# LPCB224_-_PI.net
KiCad netlist of a schematic drawn in Altium Designer
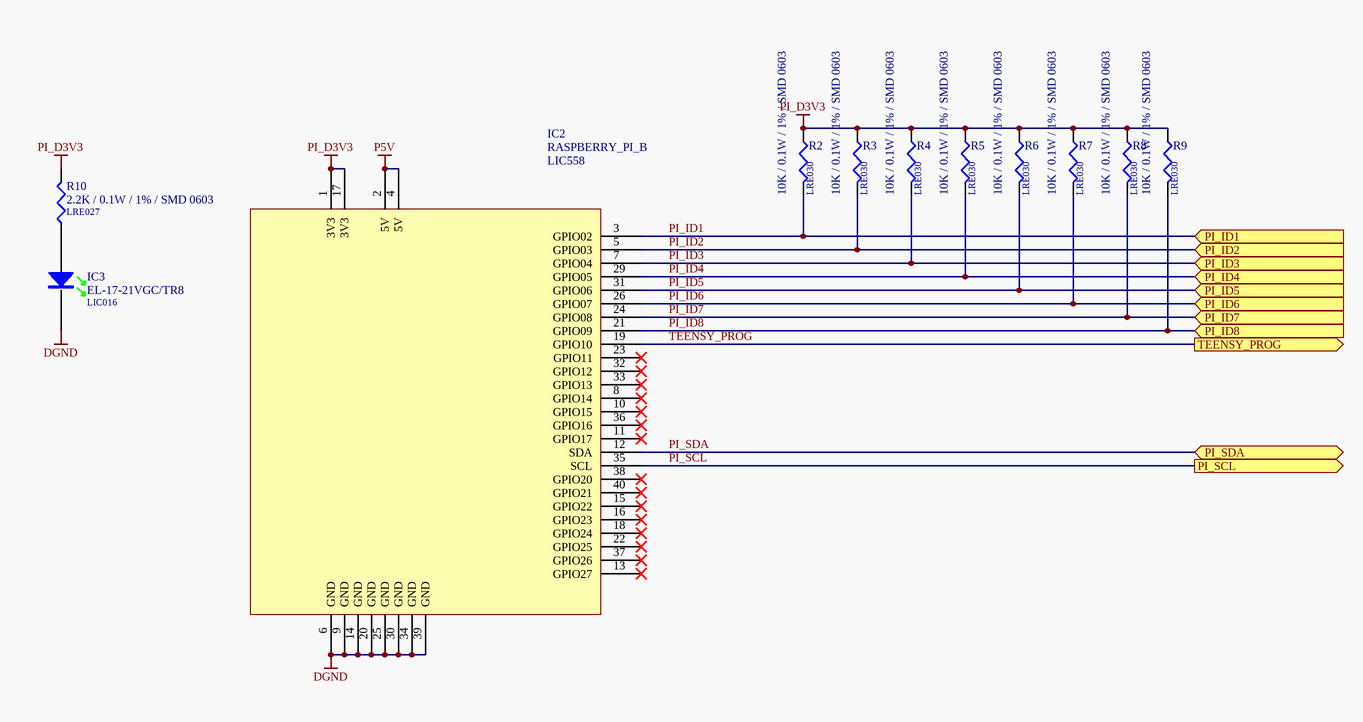
[diagram p0: LPCB224 - PI.SchDoc]

(export (version "E")
  (design (tool "Eeschema 10.0.6"))
  (components
    (comp (ref "IC2")
      (value "RASPBERRY_PI_B")
      (footprint "RASPBERRY_PI_B")
      (description "Raspberry Pi Model B")
      (fields (field (name "LDL_NUMBER") "LIC558"))
      (libsource (lib "LDL_Semiconductors") (part "RASPBERRY_PI_B"))
    )
    (comp (ref "IC3")
      (value "EL-17-21VGC/TR8")
      (footprint "CR2012-0805-LED")
      (description "LED, SMD, 0805 Green [LIC016]")
      (fields (field (name "LDL_NUMBER") "LIC016"))
      (libsource (lib "LDL_Semiconductors") (part "EL-17-21VGC/TR8"))
    )
    (comp (ref "R2")
      (value "10K / 0.1W / 1% / SMD 0603")
      (footprint "LFP020__CR1608-0603-IPC7351_B")
      (description "Resistor, Ceramic Chip, 10K, 0.1W, 1%, SMD 0603 [LRE030]")
      (fields (field (name "LDL_NUMBER") "LRE030"))
      (libsource (lib "LDL_Resistors") (part "10K / 0.1W / 1% / SMD 0603"))
    )
    (comp (ref "R3")
      (value "10K / 0.1W / 1% / SMD 0603")
      (footprint "LFP020__CR1608-0603-IPC7351_B")
      (description "Resistor, Ceramic Chip, 10K, 0.1W, 1%, SMD 0603 [LRE030]")
      (fields (field (name "LDL_NUMBER") "LRE030"))
      (libsource (lib "LDL_Resistors") (part "10K / 0.1W / 1% / SMD 0603"))
    )
    (comp (ref "R4")
      (value "10K / 0.1W / 1% / SMD 0603")
      (footprint "LFP020__CR1608-0603-IPC7351_B")
      (description "Resistor, Ceramic Chip, 10K, 0.1W, 1%, SMD 0603 [LRE030]")
      (fields (field (name "LDL_NUMBER") "LRE030"))
      (libsource (lib "LDL_Resistors") (part "10K / 0.1W / 1% / SMD 0603"))
    )
    (comp (ref "R5")
      (value "10K / 0.1W / 1% / SMD 0603")
      (footprint "LFP020__CR1608-0603-IPC7351_B")
      (description "Resistor, Ceramic Chip, 10K, 0.1W, 1%, SMD 0603 [LRE030]")
      (fields (field (name "LDL_NUMBER") "LRE030"))
      (libsource (lib "LDL_Resistors") (part "10K / 0.1W / 1% / SMD 0603"))
    )
    (comp (ref "R6")
      (value "10K / 0.1W / 1% / SMD 0603")
      (footprint "LFP020__CR1608-0603-IPC7351_B")
      (description "Resistor, Ceramic Chip, 10K, 0.1W, 1%, SMD 0603 [LRE030]")
      (fields (field (name "LDL_NUMBER") "LRE030"))
      (libsource (lib "LDL_Resistors") (part "10K / 0.1W / 1% / SMD 0603"))
    )
    (comp (ref "R7")
      (value "10K / 0.1W / 1% / SMD 0603")
      (footprint "LFP020__CR1608-0603-IPC7351_B")
      (description "Resistor, Ceramic Chip, 10K, 0.1W, 1%, SMD 0603 [LRE030]")
      (fields (field (name "LDL_NUMBER") "LRE030"))
      (libsource (lib "LDL_Resistors") (part "10K / 0.1W / 1% / SMD 0603"))
    )
    (comp (ref "R8")
      (value "10K / 0.1W / 1% / SMD 0603")
      (footprint "LFP020__CR1608-0603-IPC7351_B")
      (description "Resistor, Ceramic Chip, 10K, 0.1W, 1%, SMD 0603 [LRE030]")
      (fields (field (name "LDL_NUMBER") "LRE030"))
      (libsource (lib "LDL_Resistors") (part "10K / 0.1W / 1% / SMD 0603"))
    )
    (comp (ref "R9")
      (value "10K / 0.1W / 1% / SMD 0603")
      (footprint "LFP020__CR1608-0603-IPC7351_B")
      (description "Resistor, Ceramic Chip, 10K, 0.1W, 1%, SMD 0603 [LRE030]")
      (fields (field (name "LDL_NUMBER") "LRE030"))
      (libsource (lib "LDL_Resistors") (part "10K / 0.1W / 1% / SMD 0603"))
    )
    (comp (ref "R10")
      (value "2.2K / 0.1W / 1% / SMD 0603")
      (footprint "LFP020__CR1608-0603-IPC7351_B")
      (description "Resistor, Ceramic Chip, 2.2K, 0.1W, 1%, SMD 0603 [LRE027]")
      (fields (field (name "LDL_NUMBER") "LRE027"))
      (libsource (lib "LDL_Resistors") (part "2.2K / 0.1W / 1% / SMD 0603"))
    )
  )
  (nets
    (net (code "1") (name "/PI_ID1") (class "Default")
      (node (ref "IC2") (pin "3") (pinfunction "GPIO02_3") (pintype "passive"))
      (node (ref "R2") (pin "2") (pintype "passive"))
    )
    (net (code "2") (name "/PI_ID2") (class "Default")
      (node (ref "IC2") (pin "5") (pinfunction "GPIO03_5") (pintype "passive"))
      (node (ref "R3") (pin "2") (pintype "passive"))
    )
    (net (code "3") (name "/PI_ID3") (class "Default")
      (node (ref "IC2") (pin "7") (pinfunction "GPIO04_7") (pintype "passive"))
      (node (ref "R4") (pin "2") (pintype "passive"))
    )
    (net (code "4") (name "/PI_ID4") (class "Default")
      (node (ref "IC2") (pin "29") (pinfunction "GPIO05_29") (pintype "passive"))
      (node (ref "R5") (pin "2") (pintype "passive"))
    )
    (net (code "5") (name "/PI_ID5") (class "Default")
      (node (ref "IC2") (pin "31") (pinfunction "GPIO06_31") (pintype "passive"))
      (node (ref "R6") (pin "2") (pintype "passive"))
    )
    (net (code "6") (name "/PI_ID6") (class "Default")
      (node (ref "IC2") (pin "26") (pinfunction "GPIO07_26") (pintype "passive"))
      (node (ref "R7") (pin "2") (pintype "passive"))
    )
    (net (code "7") (name "/PI_ID7") (class "Default")
      (node (ref "IC2") (pin "24") (pinfunction "GPIO08_24") (pintype "passive"))
      (node (ref "R8") (pin "2") (pintype "passive"))
    )
    (net (code "8") (name "/PI_ID8") (class "Default")
      (node (ref "IC2") (pin "21") (pinfunction "GPIO09_21") (pintype "passive"))
      (node (ref "R9") (pin "2") (pintype "passive"))
    )
    (net (code "9") (name "/PI_SCL") (class "Default")
      (node (ref "IC2") (pin "35") (pinfunction "SCL_35") (pintype "passive"))
    )
    (net (code "10") (name "/PI_SDA") (class "Default")
      (node (ref "IC2") (pin "12") (pinfunction "SDA_12") (pintype "passive"))
    )
    (net (code "11") (name "/TEENSY_PROG") (class "Default")
      (node (ref "IC2") (pin "19") (pinfunction "GPIO10_19") (pintype "passive"))
    )
    (net (code "12") (name "DGND") (class "Default")
      (node (ref "IC2") (pin "14") (pinfunction "GND_14") (pintype "power_in"))
      (node (ref "IC2") (pin "20") (pinfunction "GND_20") (pintype "power_in"))
      (node (ref "IC2") (pin "25") (pinfunction "GND_25") (pintype "power_in"))
      (node (ref "IC2") (pin "30") (pinfunction "GND_30") (pintype "power_in"))
      (node (ref "IC2") (pin "34") (pinfunction "GND_34") (pintype "power_in"))
      (node (ref "IC2") (pin "39") (pinfunction "GND_39") (pintype "power_in"))
      (node (ref "IC2") (pin "6") (pinfunction "GND_6") (pintype "power_in"))
      (node (ref "IC2") (pin "9") (pinfunction "GND_9") (pintype "power_in"))
      (node (ref "IC3") (pin "K") (pintype "passive"))
    )
    (net (code "13") (name "Net-(IC3-PadA)") (class "Default")
      (node (ref "IC3") (pin "A") (pintype "passive"))
      (node (ref "R10") (pin "1") (pintype "passive"))
    )
    (net (code "14") (name "P5V") (class "Default")
      (node (ref "IC2") (pin "2") (pinfunction "5V_2") (pintype "power_in"))
      (node (ref "IC2") (pin "4") (pinfunction "5V_4") (pintype "power_in"))
    )
    (net (code "15") (name "PI_D3V3") (class "Default")
      (node (ref "IC2") (pin "1") (pinfunction "3V3_1") (pintype "power_in"))
      (node (ref "IC2") (pin "17") (pinfunction "3V3_17") (pintype "power_in"))
      (node (ref "R10") (pin "2") (pintype "passive"))
      (node (ref "R2") (pin "1") (pintype "passive"))
      (node (ref "R3") (pin "1") (pintype "passive"))
      (node (ref "R4") (pin "1") (pintype "passive"))
      (node (ref "R5") (pin "1") (pintype "passive"))
      (node (ref "R6") (pin "1") (pintype "passive"))
      (node (ref "R7") (pin "1") (pintype "passive"))
      (node (ref "R8") (pin "1") (pintype "passive"))
      (node (ref "R9") (pin "1") (pintype "passive"))
    )
    (net (code "16") (name "unconnected-(IC2-GPIO11-Pad23)") (class "Default")
      (node (ref "IC2") (pin "23") (pinfunction "GPIO11_23") (pintype "passive+no_connect"))
    )
    (net (code "17") (name "unconnected-(IC2-GPIO12-Pad32)") (class "Default")
      (node (ref "IC2") (pin "32") (pinfunction "GPIO12_32") (pintype "passive+no_connect"))
    )
    (net (code "18") (name "unconnected-(IC2-GPIO13-Pad33)") (class "Default")
      (node (ref "IC2") (pin "33") (pinfunction "GPIO13_33") (pintype "passive+no_connect"))
    )
    (net (code "19") (name "unconnected-(IC2-GPIO14-Pad8)") (class "Default")
      (node (ref "IC2") (pin "8") (pinfunction "GPIO14_8") (pintype "passive+no_connect"))
    )
    (net (code "20") (name "unconnected-(IC2-GPIO15-Pad10)") (class "Default")
      (node (ref "IC2") (pin "10") (pinfunction "GPIO15_10") (pintype "passive+no_connect"))
    )
    (net (code "21") (name "unconnected-(IC2-GPIO16-Pad36)") (class "Default")
      (node (ref "IC2") (pin "36") (pinfunction "GPIO16_36") (pintype "passive+no_connect"))
    )
    (net (code "22") (name "unconnected-(IC2-GPIO17-Pad11)") (class "Default")
      (node (ref "IC2") (pin "11") (pinfunction "GPIO17_11") (pintype "passive+no_connect"))
    )
    (net (code "23") (name "unconnected-(IC2-GPIO20-Pad38)") (class "Default")
      (node (ref "IC2") (pin "38") (pinfunction "GPIO20_38") (pintype "passive+no_connect"))
    )
    (net (code "24") (name "unconnected-(IC2-GPIO21-Pad40)") (class "Default")
      (node (ref "IC2") (pin "40") (pinfunction "GPIO21_40") (pintype "passive+no_connect"))
    )
    (net (code "25") (name "unconnected-(IC2-GPIO22-Pad15)") (class "Default")
      (node (ref "IC2") (pin "15") (pinfunction "GPIO22_15") (pintype "passive+no_connect"))
    )
    (net (code "26") (name "unconnected-(IC2-GPIO23-Pad16)") (class "Default")
      (node (ref "IC2") (pin "16") (pinfunction "GPIO23_16") (pintype "passive+no_connect"))
    )
    (net (code "27") (name "unconnected-(IC2-GPIO24-Pad18)") (class "Default")
      (node (ref "IC2") (pin "18") (pinfunction "GPIO24_18") (pintype "passive+no_connect"))
    )
    (net (code "28") (name "unconnected-(IC2-GPIO25-Pad22)") (class "Default")
      (node (ref "IC2") (pin "22") (pinfunction "GPIO25_22") (pintype "passive+no_connect"))
    )
    (net (code "29") (name "unconnected-(IC2-GPIO26-Pad37)") (class "Default")
      (node (ref "IC2") (pin "37") (pinfunction "GPIO26_37") (pintype "passive+no_connect"))
    )
    (net (code "30") (name "unconnected-(IC2-GPIO27-Pad13)") (class "Default")
      (node (ref "IC2") (pin "13") (pinfunction "GPIO27_13") (pintype "passive+no_connect"))
    )
  )
)
